# Integrator_Differentiator.net
KiCad netlist of a schematic drawn in Altium Designer
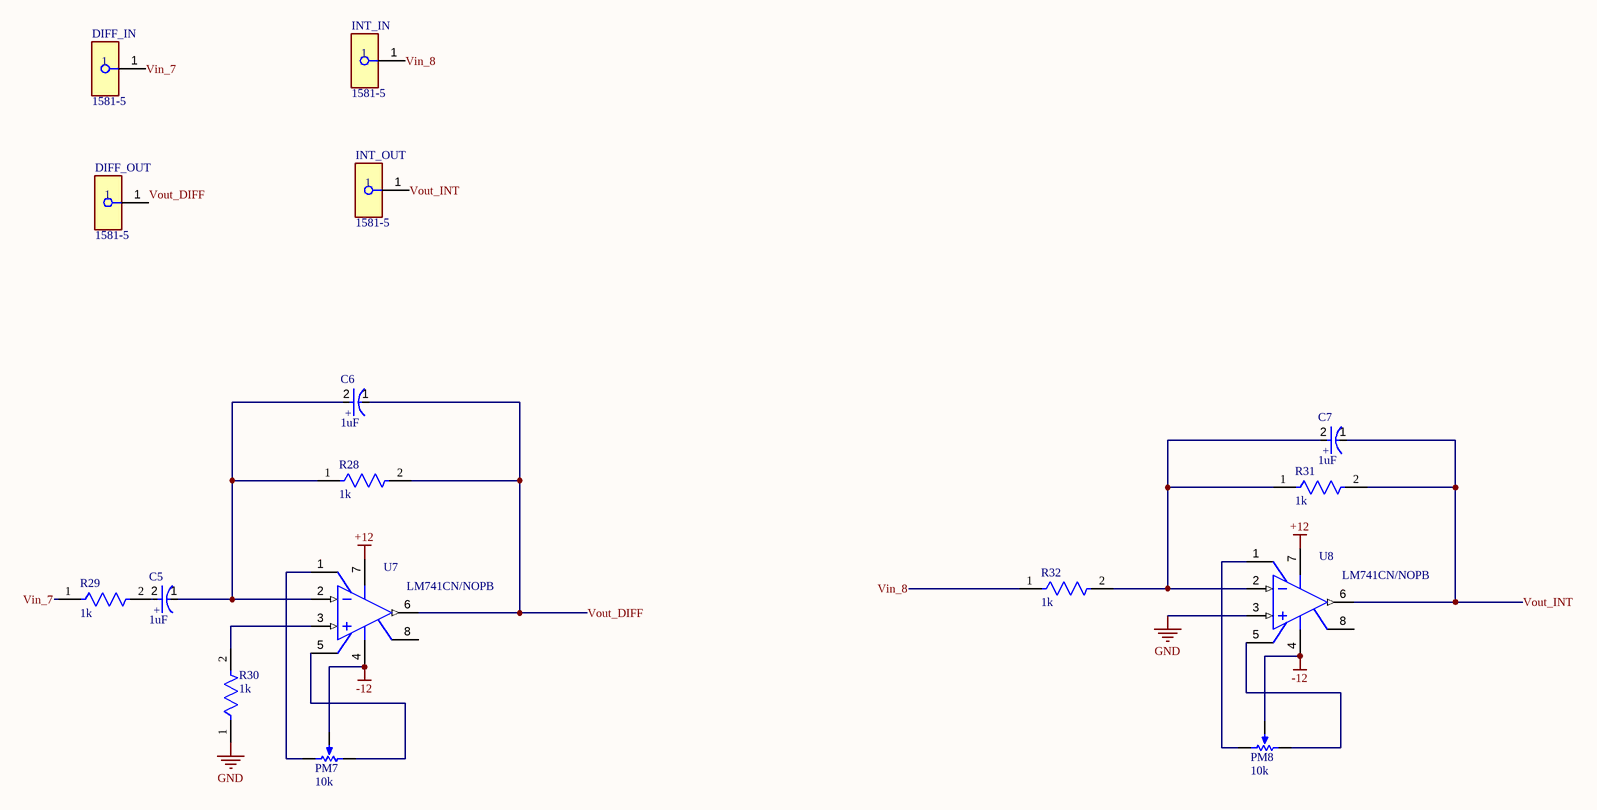
[diagram p0: Integrator_Differentiator.SchDoc]

(export (version "E")
  (design (tool "Eeschema 10.0.6"))
  (components
    (comp (ref "C5")
      (value "1uF")
      (footprint "FP-ECA-2CHG010I-MFG")
      (description "CAP ALUM 1UF 20% 160V RADIAL")
      (fields (field (name "TOLERANCE") "20%"))
      (libsource (lib "Altium Content Vault") (part "a00bbbee19879c290e62620ae7e47b1"))
    )
    (comp (ref "C6")
      (value "1uF")
      (footprint "FP-ECA-2CHG010I-MFG")
      (description "CAP ALUM 1UF 20% 160V RADIAL")
      (fields (field (name "TOLERANCE") "20%"))
      (libsource (lib "Altium Content Vault") (part "a00bbbee19879c290e62620ae7e47b1"))
    )
    (comp (ref "C7")
      (value "1uF")
      (footprint "FP-ECA-2CHG010I-MFG")
      (description "CAP ALUM 1UF 20% 160V RADIAL")
      (fields (field (name "TOLERANCE") "20%"))
      (libsource (lib "Altium Content Vault") (part "a00bbbee19879c290e62620ae7e47b1"))
    )
    (comp (ref "DIFF_IN")
      (value "1581-5")
      (footprint "FP-1581-5-MFG")
      (description "CONN BANANA JACK TURRET GREEN")
      (libsource (lib "Altium Content Vault") (part "c5c826e0c4b67fe3b42ef77f2d4decc"))
    )
    (comp (ref "DIFF_OUT")
      (value "1581-5")
      (footprint "FP-1581-5-MFG")
      (description "CONN BANANA JACK TURRET GREEN")
      (libsource (lib "Altium Content Vault") (part "c5c826e0c4b67fe3b42ef77f2d4decc"))
    )
    (comp (ref "INT_IN")
      (value "1581-5")
      (footprint "FP-1581-5-MFG")
      (description "CONN BANANA JACK TURRET GREEN")
      (libsource (lib "Altium Content Vault") (part "c5c826e0c4b67fe3b42ef77f2d4decc"))
    )
    (comp (ref "INT_OUT")
      (value "1581-5")
      (footprint "FP-1581-5-MFG")
      (description "CONN BANANA JACK TURRET GREEN")
      (libsource (lib "Altium Content Vault") (part "c5c826e0c4b67fe3b42ef77f2d4decc"))
    )
    (comp (ref "PM7")
      (value "10k")
      (footprint "BOUR-3362P")
      (description "Square Trimpot(R) Trimming Potentiometer, 10 KOhm, 300 V, -55 to 125 degC, 3-Pin THD, RoHS, Tube")
      (fields (field (name "TOLERANCE") "1%"))
      (libsource (lib "Altium Content Vault") (part "RES-POT-3"))
    )
    (comp (ref "PM8")
      (value "10k")
      (footprint "BOUR-3362P")
      (description "Square Trimpot(R) Trimming Potentiometer, 10 KOhm, 300 V, -55 to 125 degC, 3-Pin THD, RoHS, Tube")
      (fields (field (name "TOLERANCE") "1%"))
      (libsource (lib "Altium Content Vault") (part "RES-POT-3"))
    )
    (comp (ref "R28")
      (value "1k")
      (footprint "FP-RLR07-MFG")
      (fields (field (name "TOLERANCE") "1%"))
      (libsource (lib "Altium Content Vault") (part "1029c3af85768c4190bb7ad29bc67b5"))
    )
    (comp (ref "R29")
      (value "1k")
      (footprint "FP-RLR07-MFG")
      (fields (field (name "TOLERANCE") "1%"))
      (libsource (lib "Altium Content Vault") (part "1029c3af85768c4190bb7ad29bc67b5"))
    )
    (comp (ref "R30")
      (value "1k")
      (footprint "FP-RLR07-MFG")
      (fields (field (name "TOLERANCE") "1%"))
      (libsource (lib "Altium Content Vault") (part "1029c3af85768c4190bb7ad29bc67b5"))
    )
    (comp (ref "R31")
      (value "1k")
      (footprint "FP-RLR07-MFG")
      (fields (field (name "TOLERANCE") "1%"))
      (libsource (lib "Altium Content Vault") (part "1029c3af85768c4190bb7ad29bc67b5"))
    )
    (comp (ref "R32")
      (value "1k")
      (footprint "FP-RLR07-MFG")
      (fields (field (name "TOLERANCE") "1%"))
      (libsource (lib "Altium Content Vault") (part "1029c3af85768c4190bb7ad29bc67b5"))
    )
    (comp (ref "U7")
      (value "LM741CN/NOPB")
      (footprint "P0008A")
      (description "Operational Amplifier, 8-pin MDIP, Pb-Free")
      (fields (field (name "MANUFACTURER") "Texas Instruments"))
      (libsource (lib "Altium Content Vault") (part "AMP-OPA-LM741-8"))
    )
    (comp (ref "U8")
      (value "LM741CN/NOPB")
      (footprint "P0008A")
      (description "Operational Amplifier, 8-pin MDIP, Pb-Free")
      (fields (field (name "MANUFACTURER") "Texas Instruments"))
      (libsource (lib "Altium Content Vault") (part "AMP-OPA-LM741-8"))
    )
  )
  (nets
    (net (code "1") (name "+12") (class "Default")
      (node (ref "U7") (pin "7") (pinfunction "V+_7") (pintype "power_in"))
      (node (ref "U8") (pin "7") (pinfunction "V+_7") (pintype "power_in"))
    )
    (net (code "2") (name "-12") (class "Default")
      (node (ref "PM7") (pin "2") (pinfunction "S_2") (pintype "passive"))
      (node (ref "PM8") (pin "2") (pinfunction "S_2") (pintype "passive"))
      (node (ref "U7") (pin "4") (pinfunction "V-_4") (pintype "power_in"))
      (node (ref "U8") (pin "4") (pinfunction "V-_4") (pintype "power_in"))
    )
    (net (code "3") (name "/Vin_7") (class "Default")
      (node (ref "DIFF_IN") (pin "1") (pinfunction "1_1") (pintype "passive"))
      (node (ref "R29") (pin "1") (pinfunction "1_1") (pintype "passive"))
    )
    (net (code "4") (name "/Vin_8") (class "Default")
      (node (ref "INT_IN") (pin "1") (pinfunction "1_1") (pintype "passive"))
      (node (ref "R32") (pin "1") (pinfunction "1_1") (pintype "passive"))
    )
    (net (code "5") (name "/Vout_DIFF") (class "Default")
      (node (ref "C6") (pin "1") (pinfunction "C_1") (pintype "passive"))
      (node (ref "DIFF_OUT") (pin "1") (pinfunction "1_1") (pintype "passive"))
      (node (ref "R28") (pin "2") (pinfunction "2_2") (pintype "passive"))
      (node (ref "U7") (pin "6") (pinfunction "OUT_6") (pintype "output"))
    )
    (net (code "6") (name "/Vout_INT") (class "Default")
      (node (ref "C7") (pin "1") (pinfunction "C_1") (pintype "passive"))
      (node (ref "INT_OUT") (pin "1") (pinfunction "1_1") (pintype "passive"))
      (node (ref "R31") (pin "2") (pinfunction "2_2") (pintype "passive"))
      (node (ref "U8") (pin "6") (pinfunction "OUT_6") (pintype "output"))
    )
    (net (code "7") (name "GND") (class "Default")
      (node (ref "R30") (pin "1") (pinfunction "1_1") (pintype "passive"))
      (node (ref "U8") (pin "3") (pinfunction "IN+_3") (pintype "input"))
    )
    (net (code "8") (name "Net-(C5-A)") (class "Default")
      (node (ref "C5") (pin "2") (pinfunction "A_2") (pintype "passive"))
      (node (ref "R29") (pin "2") (pinfunction "2_2") (pintype "passive"))
    )
    (net (code "9") (name "Net-(C5-C)") (class "Default")
      (node (ref "C5") (pin "1") (pinfunction "C_1") (pintype "passive"))
      (node (ref "C6") (pin "2") (pinfunction "A_2") (pintype "passive"))
      (node (ref "R28") (pin "1") (pinfunction "1_1") (pintype "passive"))
      (node (ref "U7") (pin "2") (pinfunction "IN-_2") (pintype "input"))
    )
    (net (code "10") (name "Net-(C7-A)") (class "Default")
      (node (ref "C7") (pin "2") (pinfunction "A_2") (pintype "passive"))
      (node (ref "R31") (pin "1") (pinfunction "1_1") (pintype "passive"))
      (node (ref "R32") (pin "2") (pinfunction "2_2") (pintype "passive"))
      (node (ref "U8") (pin "2") (pinfunction "IN-_2") (pintype "input"))
    )
    (net (code "11") (name "Net-(PM7-CCW)") (class "Default")
      (node (ref "PM7") (pin "1") (pinfunction "CCW_1") (pintype "passive"))
      (node (ref "U7") (pin "5") (pinfunction "OFS_NULL_5") (pintype "passive"))
    )
    (net (code "12") (name "Net-(PM7-CW)") (class "Default")
      (node (ref "PM7") (pin "3") (pinfunction "CW_3") (pintype "passive"))
      (node (ref "U7") (pin "1") (pinfunction "OFS_NULL_1") (pintype "passive"))
    )
    (net (code "13") (name "Net-(PM8-CCW)") (class "Default")
      (node (ref "PM8") (pin "1") (pinfunction "CCW_1") (pintype "passive"))
      (node (ref "U8") (pin "5") (pinfunction "OFS_NULL_5") (pintype "passive"))
    )
    (net (code "14") (name "Net-(PM8-CW)") (class "Default")
      (node (ref "PM8") (pin "3") (pinfunction "CW_3") (pintype "passive"))
      (node (ref "U8") (pin "1") (pinfunction "OFS_NULL_1") (pintype "passive"))
    )
    (net (code "15") (name "Net-(U7-IN+)") (class "Default")
      (node (ref "R30") (pin "2") (pinfunction "2_2") (pintype "passive"))
      (node (ref "U7") (pin "3") (pinfunction "IN+_3") (pintype "input"))
    )
    (net (code "16") (name "unconnected-(U7-NC-Pad8)") (class "Default")
      (node (ref "U7") (pin "8") (pinfunction "NC_8") (pintype "passive"))
    )
    (net (code "17") (name "unconnected-(U8-NC-Pad8)") (class "Default")
      (node (ref "U8") (pin "8") (pinfunction "NC_8") (pintype "passive"))
    )
  )
)
